# Fan_Control.net
KiCad netlist of a schematic drawn in Altium Designer
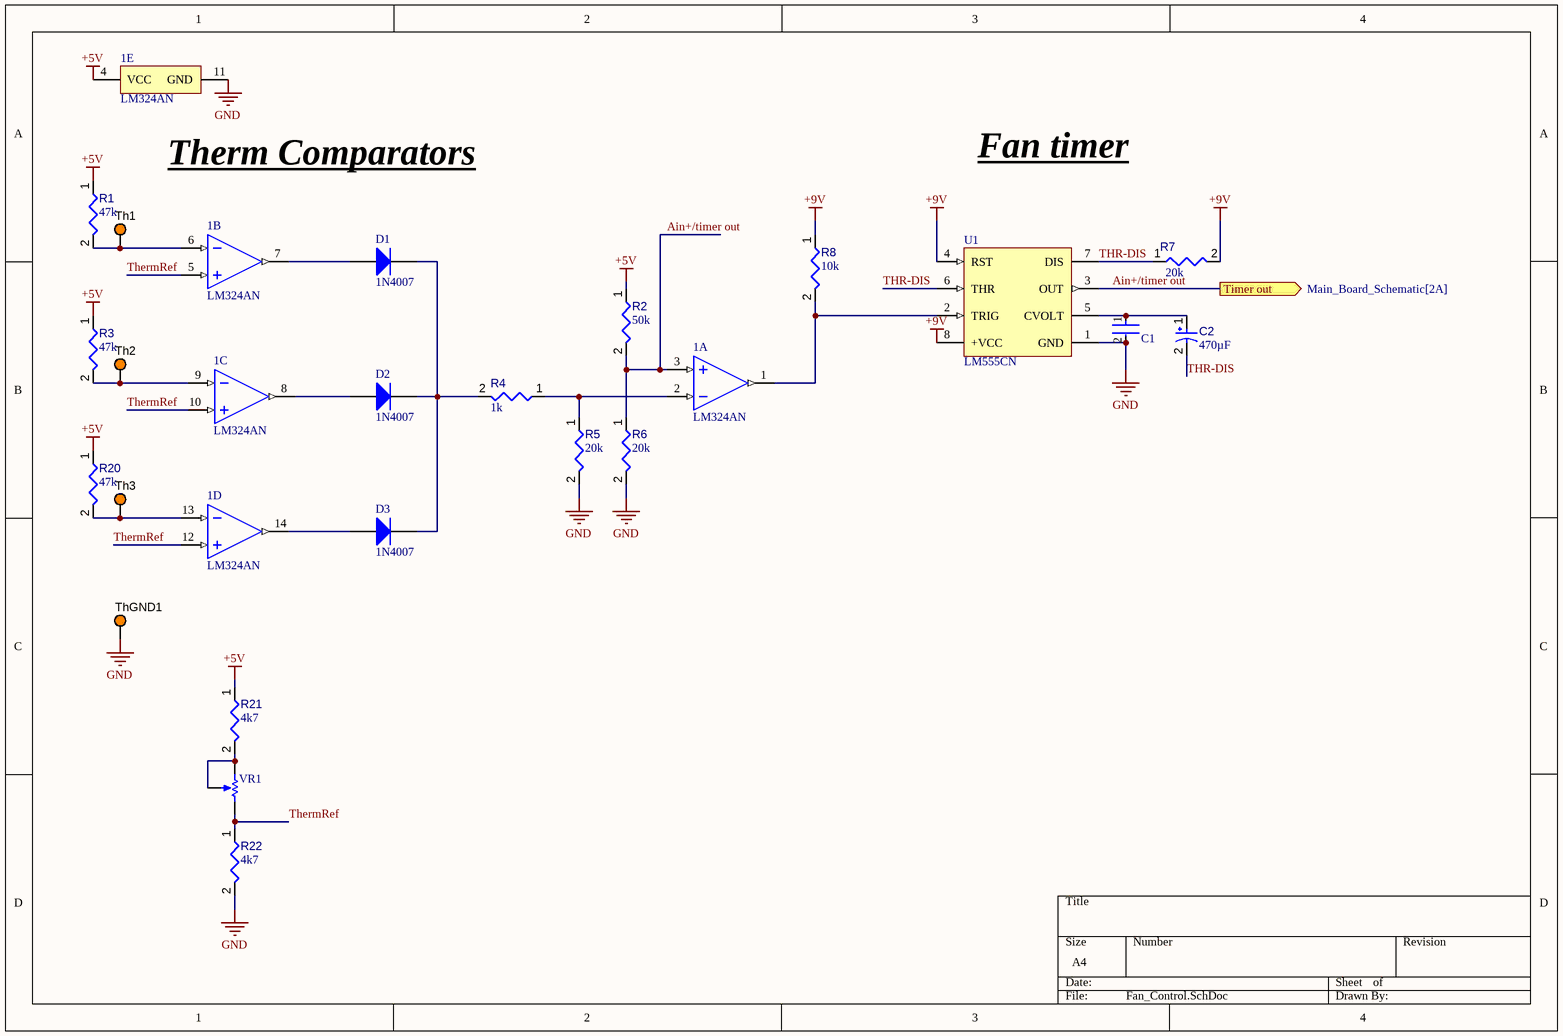
[diagram p0: Fan_Control.SchDoc]

(export (version "E")
  (design (tool "Eeschema 10.0.6"))
  (components
    (comp (ref "1")
      (value "LM324AN")
      (footprint "TI-N0014A")
      (description "Quadruple Operational Amplifier, 1.2 MHz, 0 to 70 degC, 14-Pin PDIP (N), Pb-Free (RoHS), Tube")
      (fields (field (name "MANUFACTURER") "Texas Instruments (TI)"))
      (libsource (lib "Konstantinos Psarras") (part "TI-LMX24-14"))
    )
    (comp (ref "C1")
      (value "RCER71H103K0K1H03B")
      (footprint "FP-RCE0K1-MFG")
      (description "Cap Ceramic 10nF 50V X7R ±10% Radial 5mm +125°C Automotive Bulk")
      (fields (field (name "TOLERANCE") "10%"))
      (libsource (lib "Altium Content Vault") (part "b4654b650e69147ec39a6b967a45e02"))
    )
    (comp (ref "C2")
      (value "470µF")
      (footprint "CAPPR65-350-1150X800X1250")
      (description "Aluminum Electrolytic Capacitor, 100 uF, +/- 20%, 50 V, -40 to 85 degC, 2-Pin THD, RoHS, Bulk")
      (fields (field (name "MANUFACTURER") "Panasonic") (field (name "TOLERANCE") "20%"))
      (libsource (lib "Konstantinos Psarras") (part "CAP-P-2"))
    )
    (comp (ref "D1")
      (value "1N4007")
      (footprint "FAIR-DO-41-2")
      (description "General Purpose Rectifier, 1.1 V, 1.0 A, -55 to 175 degC, 2-Pin DO-41, RoHS, Tape and Reel")
      (fields (field (name "MANUFACTURER") "Fairchild"))
      (libsource (lib "Konstantinos Psarras") (part "KESE-D_K1A2-2"))
    )
    (comp (ref "D2")
      (value "1N4007")
      (footprint "FAIR-DO-41-2")
      (description "General Purpose Rectifier, 1.1 V, 1.0 A, -55 to 175 degC, 2-Pin DO-41, RoHS, Tape and Reel")
      (fields (field (name "MANUFACTURER") "Fairchild"))
      (libsource (lib "Konstantinos Psarras") (part "KESE-D_K1A2-2"))
    )
    (comp (ref "D3")
      (value "1N4007")
      (footprint "FAIR-DO-41-2")
      (description "General Purpose Rectifier, 1.1 V, 1.0 A, -55 to 175 degC, 2-Pin DO-41, RoHS, Tape and Reel")
      (fields (field (name "MANUFACTURER") "Fairchild"))
      (libsource (lib "Konstantinos Psarras") (part "KESE-D_K1A2-2"))
    )
    (comp (ref "R1")
      (value "47k")
      (footprint "RESA60-630X240")
      (description "Axial Resistor, 100 Ohm, +/- 1%, 0.25 W, -55 to 155 degC, 2-Pin THD, RoHS, Bulk")
      (fields (field (name "MANUFACTURER") "Yageo") (field (name "TOLERANCE") "1%"))
      (libsource (lib "Konstantinos Psarras") (part "RES-2"))
    )
    (comp (ref "R2")
      (value "50k")
      (footprint "RESA60-630X240")
      (description "Axial Resistor, 100 Ohm, +/- 1%, 0.25 W, -55 to 155 degC, 2-Pin THD, RoHS, Bulk")
      (fields (field (name "MANUFACTURER") "Yageo") (field (name "TOLERANCE") "1%"))
      (libsource (lib "Konstantinos Psarras") (part "RES-2"))
    )
    (comp (ref "R3")
      (value "47k")
      (footprint "RESA60-630X240")
      (description "Axial Resistor, 100 Ohm, +/- 1%, 0.25 W, -55 to 155 degC, 2-Pin THD, RoHS, Bulk")
      (fields (field (name "MANUFACTURER") "Yageo") (field (name "TOLERANCE") "1%"))
      (libsource (lib "Konstantinos Psarras") (part "RES-2"))
    )
    (comp (ref "R4")
      (value "1k")
      (footprint "RESA60-630X240")
      (description "Axial Resistor, 100 Ohm, +/- 1%, 0.25 W, -55 to 155 degC, 2-Pin THD, RoHS, Bulk")
      (fields (field (name "MANUFACTURER") "Yageo") (field (name "TOLERANCE") "1%"))
      (libsource (lib "Konstantinos Psarras") (part "RES-2"))
    )
    (comp (ref "R5")
      (value "20k")
      (footprint "RESA60-630X240")
      (description "Axial Resistor, 100 Ohm, +/- 1%, 0.25 W, -55 to 155 degC, 2-Pin THD, RoHS, Bulk")
      (fields (field (name "MANUFACTURER") "Yageo") (field (name "TOLERANCE") "1%"))
      (libsource (lib "Konstantinos Psarras") (part "RES-2"))
    )
    (comp (ref "R6")
      (value "20k")
      (footprint "RESA60-630X240")
      (description "Axial Resistor, 100 Ohm, +/- 1%, 0.25 W, -55 to 155 degC, 2-Pin THD, RoHS, Bulk")
      (fields (field (name "MANUFACTURER") "Yageo") (field (name "TOLERANCE") "1%"))
      (libsource (lib "Konstantinos Psarras") (part "RES-2"))
    )
    (comp (ref "R7")
      (value "20k")
      (footprint "RESA60-630X240")
      (description "Axial Resistor, 1 KOhm, +/- 1%, 250 mW, -55 to 155 degC, 2-Pin THD, RoHS, Bulk")
      (fields (field (name "TOLERANCE") "1%") (field (name "POWER") "250mW"))
      (libsource (lib "Konstantinos Psarras") (part "RES-2"))
    )
    (comp (ref "R8")
      (value "10k")
      (footprint "RESA60-630X240")
      (description "Axial Resistor, 1 KOhm, +/- 1%, 250 mW, -55 to 155 degC, 2-Pin THD, RoHS, Bulk")
      (fields (field (name "TOLERANCE") "1%") (field (name "POWER") "250mW"))
      (libsource (lib "Konstantinos Psarras") (part "RES-2"))
    )
    (comp (ref "R20")
      (value "47k")
      (footprint "RESA60-630X240")
      (description "Axial Resistor, 100 Ohm, +/- 1%, 0.25 W, -55 to 155 degC, 2-Pin THD, RoHS, Bulk")
      (fields (field (name "MANUFACTURER") "Yageo") (field (name "TOLERANCE") "1%"))
      (libsource (lib "Konstantinos Psarras") (part "RES-2"))
    )
    (comp (ref "R21")
      (value "4k7")
      (footprint "RESA60-630X240")
      (description "Axial Resistor, 100 Ohm, +/- 1%, 0.25 W, -55 to 155 degC, 2-Pin THD, RoHS, Bulk")
      (fields (field (name "MANUFACTURER") "Yageo") (field (name "TOLERANCE") "1%"))
      (libsource (lib "Konstantinos Psarras") (part "RES-2"))
    )
    (comp (ref "R22")
      (value "4k7")
      (footprint "RESA60-630X240")
      (description "Axial Resistor, 100 Ohm, +/- 1%, 0.25 W, -55 to 155 degC, 2-Pin THD, RoHS, Bulk")
      (fields (field (name "MANUFACTURER") "Yageo") (field (name "TOLERANCE") "1%"))
      (libsource (lib "Konstantinos Psarras") (part "RES-2"))
    )
    (comp (ref "Th1")
      (value "5003")
      (footprint "KSTN-5003")
      (description "Test Point, Orange, Height 4.6 mm, Tail Length 3 mm, 1-Pin THD, RoHS")
      (fields (field (name "MANUFACTURER") "Keystone"))
      (libsource (lib "Konstantinos Psarras") (part "TESTPOINT_ORANGE"))
    )
    (comp (ref "Th2")
      (value "5003")
      (footprint "KSTN-5003")
      (description "Test Point, Orange, Height 4.6 mm, Tail Length 3 mm, 1-Pin THD, RoHS")
      (fields (field (name "MANUFACTURER") "Keystone"))
      (libsource (lib "Konstantinos Psarras") (part "TESTPOINT_ORANGE"))
    )
    (comp (ref "Th3")
      (value "5003")
      (footprint "KSTN-5003")
      (description "Test Point, Orange, Height 4.6 mm, Tail Length 3 mm, 1-Pin THD, RoHS")
      (fields (field (name "MANUFACTURER") "Keystone"))
      (libsource (lib "Konstantinos Psarras") (part "TESTPOINT_ORANGE"))
    )
    (comp (ref "ThGND1")
      (value "5003")
      (footprint "KSTN-5003")
      (description "Test Point, Orange, Height 4.6 mm, Tail Length 3 mm, 1-Pin THD, RoHS")
      (fields (field (name "MANUFACTURER") "Keystone"))
      (libsource (lib "Konstantinos Psarras") (part "TESTPOINT_ORANGE"))
    )
    (comp (ref "U1")
      (value "LM555CN")
      (footprint "N08E")
      (description "Timer, 8-pin MDIP")
      (fields (field (name "MANUFACTURER") "National Semiconductor"))
      (libsource (lib "Altium Content Vault") (part "AN-TIMER-LM555-8"))
    )
    (comp (ref "VR1")
      (value "3362P-1-104LF")
      (footprint "BOUR-3362P")
      (description "Square Trimpot(R) Trimming Potentiometer, 100 KOhm, 300 V, -55 to 125 degC, 3-Pin THD, RoHS, Tube")
      (fields (field (name "MANUFACTURER") "Bourns") (field (name "POWER") "500mW"))
      (libsource (lib "Konstantinos Psarras") (part "RES-POT-3"))
    )
  )
  (nets
    (net (code "1") (name "+5V") (class "Default")
      (node (ref "1") (pin "4") (pinfunction "VCC_4") (pintype "power_in"))
      (node (ref "R1") (pin "1") (pinfunction "1_1") (pintype "passive"))
      (node (ref "R2") (pin "1") (pinfunction "1_1") (pintype "passive"))
      (node (ref "R20") (pin "1") (pinfunction "1_1") (pintype "passive"))
      (node (ref "R21") (pin "1") (pinfunction "1_1") (pintype "passive"))
      (node (ref "R3") (pin "1") (pinfunction "1_1") (pintype "passive"))
    )
    (net (code "2") (name "+9V") (class "Default")
      (node (ref "R7") (pin "2") (pinfunction "2_2") (pintype "passive"))
      (node (ref "R8") (pin "1") (pinfunction "1_1") (pintype "passive"))
      (node (ref "U1") (pin "4") (pinfunction "RST_4") (pintype "input"))
      (node (ref "U1") (pin "8") (pinfunction "+VCC_8") (pintype "power_in"))
    )
    (net (code "3") (name "/Ain+{slash}timer out") (class "Default")
      (node (ref "1") (pin "3") (pinfunction "1IN+_3") (pintype "input"))
      (node (ref "R2") (pin "2") (pinfunction "2_2") (pintype "passive"))
      (node (ref "R6") (pin "1") (pinfunction "1_1") (pintype "passive"))
      (node (ref "U1") (pin "3") (pinfunction "OUT_3") (pintype "output"))
    )
    (net (code "4") (name "/THR-DIS") (class "Default")
      (node (ref "C2") (pin "2") (pinfunction "2_2") (pintype "passive"))
      (node (ref "R7") (pin "1") (pinfunction "1_1") (pintype "passive"))
      (node (ref "U1") (pin "6") (pinfunction "THR_6") (pintype "input"))
      (node (ref "U1") (pin "7") (pinfunction "DIS_7") (pintype "open_collector"))
    )
    (net (code "5") (name "/ThermRef") (class "Default")
      (node (ref "1") (pin "10") (pinfunction "3IN+_10") (pintype "input"))
      (node (ref "1") (pin "12") (pinfunction "4IN+_12") (pintype "input"))
      (node (ref "1") (pin "5") (pinfunction "2IN+_5") (pintype "input"))
      (node (ref "R22") (pin "1") (pinfunction "1_1") (pintype "passive"))
      (node (ref "VR1") (pin "3") (pinfunction "CW_3") (pintype "passive"))
    )
    (net (code "6") (name "GND") (class "Default")
      (node (ref "1") (pin "11") (pinfunction "GND_11") (pintype "power_in"))
      (node (ref "C1") (pin "2") (pinfunction "2_2") (pintype "passive"))
      (node (ref "R22") (pin "2") (pinfunction "2_2") (pintype "passive"))
      (node (ref "R5") (pin "2") (pinfunction "2_2") (pintype "passive"))
      (node (ref "R6") (pin "2") (pinfunction "2_2") (pintype "passive"))
      (node (ref "ThGND1") (pin "1") (pinfunction "1_1") (pintype "passive"))
      (node (ref "U1") (pin "1") (pinfunction "GND_1") (pintype "power_in"))
    )
    (net (code "7") (name "Net-(1A-1IN-)") (class "Default")
      (node (ref "1") (pin "2") (pinfunction "1IN-_2") (pintype "input"))
      (node (ref "R4") (pin "1") (pinfunction "1_1") (pintype "passive"))
      (node (ref "R5") (pin "1") (pinfunction "1_1") (pintype "passive"))
    )
    (net (code "8") (name "Net-(1A-1OUT)") (class "Default")
      (node (ref "1") (pin "1") (pinfunction "1OUT_1") (pintype "output"))
      (node (ref "R8") (pin "2") (pinfunction "2_2") (pintype "passive"))
      (node (ref "U1") (pin "2") (pinfunction "TRIG_2") (pintype "input"))
    )
    (net (code "9") (name "Net-(1B-2IN-)") (class "Default")
      (node (ref "1") (pin "6") (pinfunction "2IN-_6") (pintype "input"))
      (node (ref "R1") (pin "2") (pinfunction "2_2") (pintype "passive"))
      (node (ref "Th1") (pin "1") (pinfunction "1_1") (pintype "passive"))
    )
    (net (code "10") (name "Net-(1B-2OUT)") (class "Default")
      (node (ref "1") (pin "7") (pinfunction "2OUT_7") (pintype "output"))
      (node (ref "D1") (pin "2") (pinfunction "A_2") (pintype "passive"))
    )
    (net (code "11") (name "Net-(1C-3IN-)") (class "Default")
      (node (ref "1") (pin "9") (pinfunction "3IN-_9") (pintype "input"))
      (node (ref "R3") (pin "2") (pinfunction "2_2") (pintype "passive"))
      (node (ref "Th2") (pin "1") (pinfunction "1_1") (pintype "passive"))
    )
    (net (code "12") (name "Net-(1C-3OUT)") (class "Default")
      (node (ref "1") (pin "8") (pinfunction "3OUT_8") (pintype "output"))
      (node (ref "D2") (pin "2") (pinfunction "A_2") (pintype "passive"))
    )
    (net (code "13") (name "Net-(1D-4IN-)") (class "Default")
      (node (ref "1") (pin "13") (pinfunction "4IN-_13") (pintype "input"))
      (node (ref "R20") (pin "2") (pinfunction "2_2") (pintype "passive"))
      (node (ref "Th3") (pin "1") (pinfunction "1_1") (pintype "passive"))
    )
    (net (code "14") (name "Net-(1D-4OUT)") (class "Default")
      (node (ref "1") (pin "14") (pinfunction "4OUT_14") (pintype "output"))
      (node (ref "D3") (pin "2") (pinfunction "A_2") (pintype "passive"))
    )
    (net (code "15") (name "Net-(D1-K)") (class "Default")
      (node (ref "D1") (pin "1") (pinfunction "K_1") (pintype "passive"))
      (node (ref "D2") (pin "1") (pinfunction "K_1") (pintype "passive"))
      (node (ref "D3") (pin "1") (pinfunction "K_1") (pintype "passive"))
      (node (ref "R4") (pin "2") (pinfunction "2_2") (pintype "passive"))
    )
    (net (code "16") (name "Net-(U1-CVOLT)") (class "Default")
      (node (ref "C1") (pin "1") (pinfunction "1_1") (pintype "passive"))
      (node (ref "C2") (pin "1") (pinfunction "1_1") (pintype "passive"))
      (node (ref "U1") (pin "5") (pinfunction "CVOLT_5") (pintype "passive"))
    )
    (net (code "17") (name "Net-(VR1-CCW)") (class "Default")
      (node (ref "R21") (pin "2") (pinfunction "2_2") (pintype "passive"))
      (node (ref "VR1") (pin "1") (pinfunction "CCW_1") (pintype "passive"))
      (node (ref "VR1") (pin "2") (pinfunction "S_2") (pintype "passive"))
    )
  )
)
